# 03_FT2232-jtag.net
KiCad netlist of a schematic drawn in Altium Designer
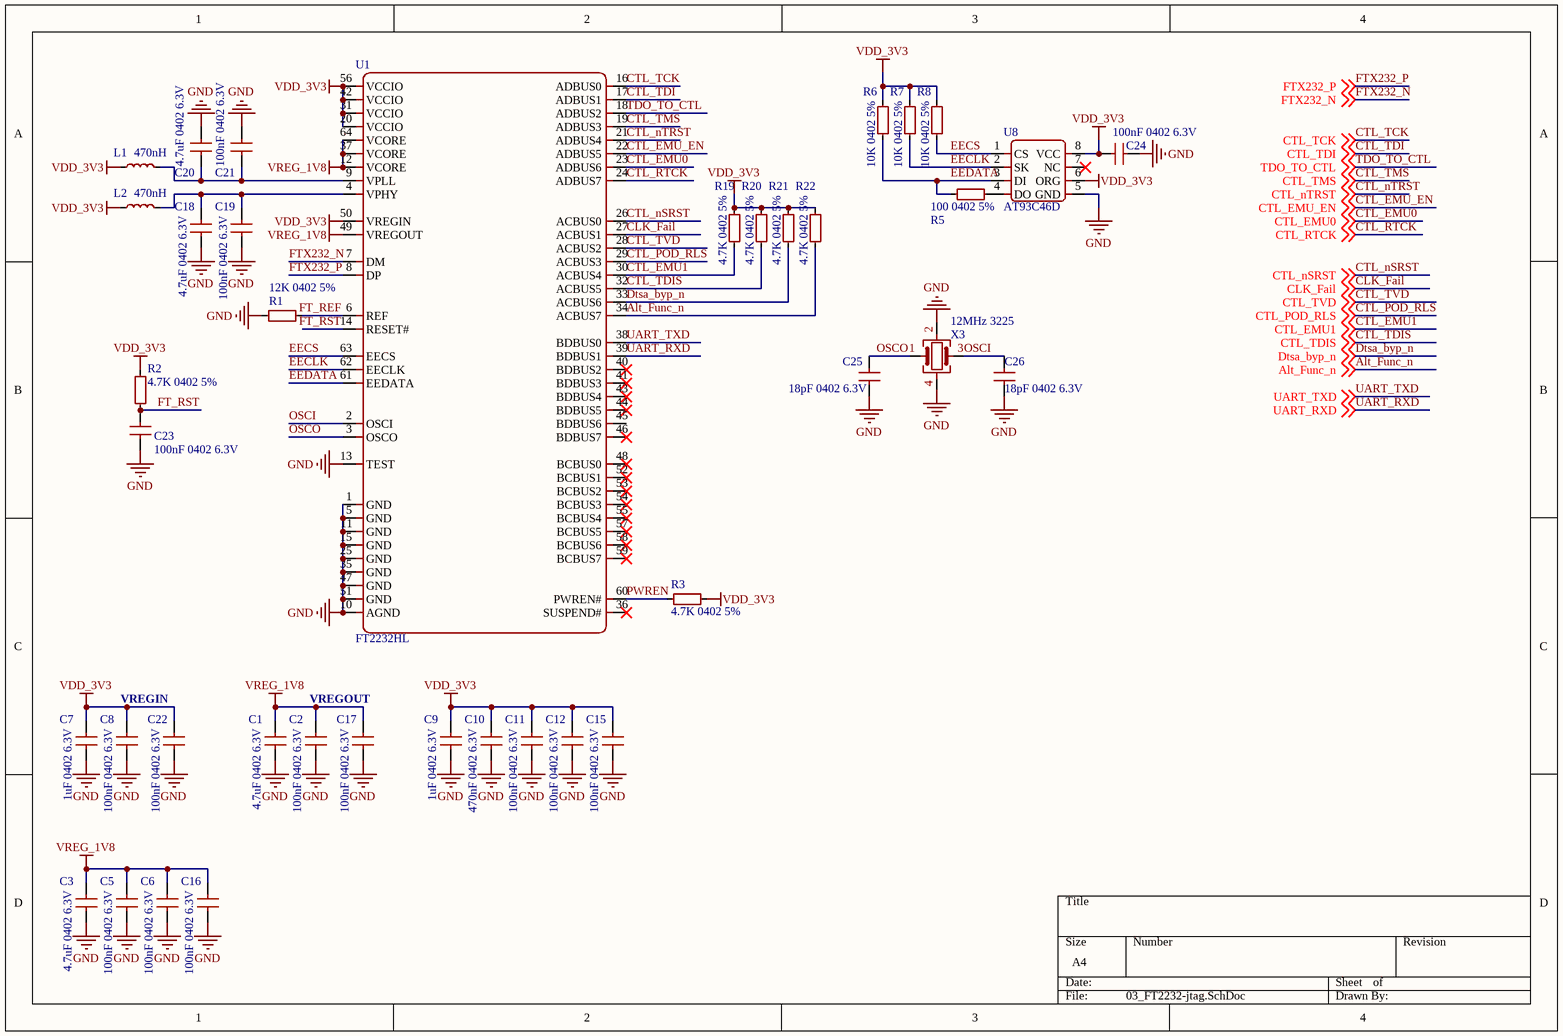
[diagram p0: 03_FT2232-jtag.SchDoc]

(export (version "E")
  (design (tool "Eeschema 10.0.6"))
  (components
    (comp (ref "C1")
      (value "4.7uF 0402 6.3V")
      (footprint "C_0402_1005Metric")
      (description "Unpolarized capacitor")
      (libsource (lib "FPGA_VGA") (part "C"))
    )
    (comp (ref "C2")
      (value "100nF 0402 6.3V")
      (footprint "C_0402_1005Metric")
      (description "Unpolarized capacitor")
      (libsource (lib "FPGA_VGA") (part "C"))
    )
    (comp (ref "C3")
      (value "4.7uF 0402 6.3V")
      (footprint "C_0402_1005Metric")
      (description "Unpolarized capacitor")
      (libsource (lib "FPGA_VGA") (part "C"))
    )
    (comp (ref "C5")
      (value "100nF 0402 6.3V")
      (footprint "C_0402_1005Metric")
      (description "Unpolarized capacitor")
      (libsource (lib "FPGA_VGA") (part "C"))
    )
    (comp (ref "C6")
      (value "100nF 0402 6.3V")
      (footprint "C_0402_1005Metric")
      (description "Unpolarized capacitor")
      (libsource (lib "FPGA_VGA") (part "C"))
    )
    (comp (ref "C7")
      (value "1uF 0402 6.3V")
      (footprint "C_0402_1005Metric")
      (description "Unpolarized capacitor")
      (libsource (lib "FPGA_VGA") (part "C"))
    )
    (comp (ref "C8")
      (value "100nF 0402 6.3V")
      (footprint "C_0402_1005Metric")
      (description "Unpolarized capacitor")
      (libsource (lib "FPGA_VGA") (part "C"))
    )
    (comp (ref "C9")
      (value "1uF 0402 6.3V")
      (footprint "C_0402_1005Metric")
      (description "Unpolarized capacitor")
      (libsource (lib "FPGA_VGA") (part "C"))
    )
    (comp (ref "C10")
      (value "470nF 0402 6.3V")
      (footprint "C_0402_1005Metric")
      (description "Unpolarized capacitor")
      (libsource (lib "FPGA_VGA") (part "C"))
    )
    (comp (ref "C11")
      (value "100nF 0402 6.3V")
      (footprint "C_0402_1005Metric")
      (description "Unpolarized capacitor")
      (libsource (lib "FPGA_VGA") (part "C"))
    )
    (comp (ref "C12")
      (value "100nF 0402 6.3V")
      (footprint "C_0402_1005Metric")
      (description "Unpolarized capacitor")
      (libsource (lib "FPGA_VGA") (part "C"))
    )
    (comp (ref "C15")
      (value "100nF 0402 6.3V")
      (footprint "C_0402_1005Metric")
      (description "Unpolarized capacitor")
      (libsource (lib "FPGA_VGA") (part "C"))
    )
    (comp (ref "C16")
      (value "100nF 0402 6.3V")
      (footprint "C_0402_1005Metric")
      (description "Unpolarized capacitor")
      (libsource (lib "FPGA_VGA") (part "C"))
    )
    (comp (ref "C17")
      (value "100nF 0402 6.3V")
      (footprint "C_0402_1005Metric")
      (description "Unpolarized capacitor")
      (libsource (lib "FPGA_VGA") (part "C"))
    )
    (comp (ref "C18")
      (value "4.7uF 0402 6.3V")
      (footprint "C_0402_1005Metric")
      (description "Unpolarized capacitor")
      (libsource (lib "FPGA_VGA") (part "C"))
    )
    (comp (ref "C19")
      (value "100nF 0402 6.3V")
      (footprint "C_0402_1005Metric")
      (description "Unpolarized capacitor")
      (libsource (lib "FPGA_VGA") (part "C"))
    )
    (comp (ref "C20")
      (value "100nF 0402 6.3V")
      (footprint "C_0402_1005Metric")
      (description "Unpolarized capacitor")
      (libsource (lib "FPGA_VGA") (part "C"))
    )
    (comp (ref "C21")
      (value "4.7uF 0402 6.3V")
      (footprint "C_0402_1005Metric")
      (description "Unpolarized capacitor")
      (libsource (lib "FPGA_VGA") (part "C"))
    )
    (comp (ref "C22")
      (value "100nF 0402 6.3V")
      (footprint "C_0402_1005Metric")
      (description "Unpolarized capacitor")
      (libsource (lib "FPGA_VGA") (part "C"))
    )
    (comp (ref "C23")
      (value "100nF 0402 6.3V")
      (footprint "C_0402_1005Metric")
      (description "Unpolarized capacitor")
      (libsource (lib "FPGA_VGA") (part "C"))
    )
    (comp (ref "C24")
      (value "100nF 0402 6.3V")
      (footprint "C_0402_1005Metric")
      (description "Unpolarized capacitor")
      (libsource (lib "FPGA_VGA") (part "C"))
    )
    (comp (ref "C25")
      (value "18pF 0402 6.3V")
      (footprint "C_0402_1005Metric")
      (description "Unpolarized capacitor")
      (libsource (lib "FPGA_VGA") (part "C"))
    )
    (comp (ref "C26")
      (value "18pF 0402 6.3V")
      (footprint "C_0402_1005Metric")
      (description "Unpolarized capacitor")
      (libsource (lib "FPGA_VGA") (part "C"))
    )
    (comp (ref "L1")
      (value "470nH")
      (footprint "L0402-SMD")
      (description "Inductor")
      (libsource (lib "FPGA_FTX232HL") (part "L"))
    )
    (comp (ref "L2")
      (value "470nH")
      (footprint "L0402-SMD")
      (description "Inductor")
      (libsource (lib "FPGA_FTX232HL") (part "L"))
    )
    (comp (ref "R1")
      (value "12K 0402 5%")
      (footprint "R_0402_1005Metric")
      (description "Resistor")
      (libsource (lib "FPGA_VGA") (part "R"))
    )
    (comp (ref "R2")
      (value "4.7K 0402 5%")
      (footprint "R_0402_1005Metric")
      (description "Resistor")
      (libsource (lib "FPGA_VGA") (part "R"))
    )
    (comp (ref "R3")
      (value "4.7K 0402 5%")
      (footprint "R_0402_1005Metric")
      (description "Resistor")
      (libsource (lib "FPGA_VGA") (part "R"))
    )
    (comp (ref "R5")
      (value "100 0402 5%")
      (footprint "R_0402_1005Metric")
      (description "Resistor")
      (libsource (lib "FPGA_VGA") (part "R"))
    )
    (comp (ref "R6")
      (value "10K 0402 5%")
      (footprint "R_0402_1005Metric")
      (description "Resistor")
      (libsource (lib "FPGA_VGA") (part "R"))
    )
    (comp (ref "R7")
      (value "10K 0402 5%")
      (footprint "R_0402_1005Metric")
      (description "Resistor")
      (libsource (lib "FPGA_VGA") (part "R"))
    )
    (comp (ref "R8")
      (value "10K 0402 5%")
      (footprint "R_0402_1005Metric")
      (description "Resistor")
      (libsource (lib "FPGA_VGA") (part "R"))
    )
    (comp (ref "R19")
      (value "4.7K 0402 5%")
      (footprint "R_0402_1005Metric")
      (description "Resistor")
      (libsource (lib "FPGA_VGA") (part "R"))
    )
    (comp (ref "R20")
      (value "4.7K 0402 5%")
      (footprint "R_0402_1005Metric")
      (description "Resistor")
      (libsource (lib "FPGA_VGA") (part "R"))
    )
    (comp (ref "R21")
      (value "4.7K 0402 5%")
      (footprint "R_0402_1005Metric")
      (description "Resistor")
      (libsource (lib "FPGA_VGA") (part "R"))
    )
    (comp (ref "R22")
      (value "4.7K 0402 5%")
      (footprint "R_0402_1005Metric")
      (description "Resistor")
      (libsource (lib "FPGA_VGA") (part "R"))
    )
    (comp (ref "U1")
      (value "FT2232HL")
      (footprint "FT2232HL-LQFP-64-HD")
      (description "FT2232H Dual High Speed USB to Multipurpose UART/FIFO IC")
      (libsource (lib "XDS100V3-anlogic") (part "FT2232HL"))
    )
    (comp (ref "U8")
      (value "AT93C46D")
      (footprint "AT93C46DN")
      (description "Three-Wire Automotive Temperature Serial EEPROM 1-Kbit")
      (libsource (lib "FPGA_VGA") (part "AT93C46D"))
    )
    (comp (ref "X3")
      (value "12MHz 3225")
      (footprint "Crystal_SMD_3225-4Pin_3.2x2.5mm - duplicate")
      (libsource (lib "FPGA_VGA") (part "Crystal-4Pin-Passive-GND24"))
    )
  )
  (nets
    (net (code "1") (name "/EECLK") (class "Default")
      (node (ref "R7") (pin "2") (pinfunction "2_2") (pintype "passive"))
      (node (ref "U1") (pin "62") (pinfunction "EECLK_62") (pintype "passive"))
      (node (ref "U8") (pin "2") (pinfunction "SK_2") (pintype "passive"))
    )
    (net (code "2") (name "/EECS") (class "Default")
      (node (ref "R8") (pin "2") (pinfunction "2_2") (pintype "passive"))
      (node (ref "U1") (pin "63") (pinfunction "EECS_63") (pintype "passive"))
      (node (ref "U8") (pin "1") (pinfunction "CS_1") (pintype "passive"))
    )
    (net (code "3") (name "/EEDATA") (class "Default")
      (node (ref "R5") (pin "1") (pinfunction "1_1") (pintype "passive"))
      (node (ref "R6") (pin "2") (pinfunction "2_2") (pintype "passive"))
      (node (ref "U1") (pin "61") (pinfunction "EEDATA_61") (pintype "passive"))
      (node (ref "U8") (pin "3") (pinfunction "DI_3") (pintype "passive"))
    )
    (net (code "4") (name "/FT_REF") (class "Default")
      (node (ref "R1") (pin "2") (pinfunction "2_2") (pintype "passive"))
      (node (ref "U1") (pin "6") (pinfunction "REF_6") (pintype "passive"))
    )
    (net (code "5") (name "/FT_RST") (class "Default")
      (node (ref "C23") (pin "2") (pinfunction "2_2") (pintype "passive"))
      (node (ref "R2") (pin "2") (pinfunction "2_2") (pintype "passive"))
      (node (ref "U1") (pin "14") (pinfunction "RESET#_14") (pintype "passive"))
    )
    (net (code "6") (name "/OSCI") (class "Default")
      (node (ref "C26") (pin "1") (pinfunction "1_1") (pintype "passive"))
      (node (ref "U1") (pin "2") (pinfunction "OSCI_2") (pintype "passive"))
      (node (ref "X3") (pin "3") (pinfunction "3_3") (pintype "passive"))
    )
    (net (code "7") (name "/OSCO") (class "Default")
      (node (ref "C25") (pin "1") (pinfunction "1_1") (pintype "passive"))
      (node (ref "U1") (pin "3") (pinfunction "OSCO_3") (pintype "passive"))
      (node (ref "X3") (pin "1") (pinfunction "1_1") (pintype "passive"))
    )
    (net (code "8") (name "/PWREN") (class "Default")
      (node (ref "R3") (pin "2") (pinfunction "2_2") (pintype "passive"))
      (node (ref "U1") (pin "60") (pinfunction "PWREN#_60") (pintype "passive"))
    )
    (net (code "9") (name "Alt_Func_n") (class "Default")
      (node (ref "R22") (pin "1") (pinfunction "1_1") (pintype "passive"))
      (node (ref "U1") (pin "34") (pinfunction "ACBUS7_34") (pintype "passive"))
    )
    (net (code "10") (name "CLK_Fail") (class "Default")
      (node (ref "U1") (pin "27") (pinfunction "ACBUS1_27") (pintype "passive"))
    )
    (net (code "11") (name "CTL_EMU0") (class "Default")
      (node (ref "U1") (pin "23") (pinfunction "ADBUS6_23") (pintype "passive"))
    )
    (net (code "12") (name "CTL_EMU1") (class "Default")
      (node (ref "R19") (pin "1") (pinfunction "1_1") (pintype "passive"))
      (node (ref "U1") (pin "30") (pinfunction "ACBUS4_30") (pintype "passive"))
    )
    (net (code "13") (name "CTL_EMU_EN") (class "Default")
      (node (ref "U1") (pin "22") (pinfunction "ADBUS5_22") (pintype "passive"))
    )
    (net (code "14") (name "CTL_POD_RLS") (class "Default")
      (node (ref "U1") (pin "29") (pinfunction "ACBUS3_29") (pintype "passive"))
    )
    (net (code "15") (name "CTL_RTCK") (class "Default")
      (node (ref "U1") (pin "24") (pinfunction "ADBUS7_24") (pintype "passive"))
    )
    (net (code "16") (name "CTL_TCK") (class "Default")
      (node (ref "U1") (pin "16") (pinfunction "ADBUS0_16") (pintype "passive"))
    )
    (net (code "17") (name "CTL_TDI") (class "Default")
      (node (ref "U1") (pin "17") (pinfunction "ADBUS1_17") (pintype "passive"))
    )
    (net (code "18") (name "CTL_TDIS") (class "Default")
      (node (ref "R20") (pin "1") (pinfunction "1_1") (pintype "passive"))
      (node (ref "U1") (pin "32") (pinfunction "ACBUS5_32") (pintype "passive"))
    )
    (net (code "19") (name "CTL_TMS") (class "Default")
      (node (ref "U1") (pin "19") (pinfunction "ADBUS3_19") (pintype "passive"))
    )
    (net (code "20") (name "CTL_TVD") (class "Default")
      (node (ref "U1") (pin "28") (pinfunction "ACBUS2_28") (pintype "passive"))
    )
    (net (code "21") (name "CTL_nSRST") (class "Default")
      (node (ref "U1") (pin "26") (pinfunction "ACBUS0_26") (pintype "passive"))
    )
    (net (code "22") (name "CTL_nTRST") (class "Default")
      (node (ref "U1") (pin "21") (pinfunction "ADBUS4_21") (pintype "passive"))
    )
    (net (code "23") (name "Dtsa_byp_n") (class "Default")
      (node (ref "R21") (pin "1") (pinfunction "1_1") (pintype "passive"))
      (node (ref "U1") (pin "33") (pinfunction "ACBUS6_33") (pintype "passive"))
    )
    (net (code "24") (name "FTX232_N") (class "Default")
      (node (ref "U1") (pin "7") (pinfunction "DM_7") (pintype "passive"))
    )
    (net (code "25") (name "FTX232_P") (class "Default")
      (node (ref "U1") (pin "8") (pinfunction "DP_8") (pintype "passive"))
    )
    (net (code "26") (name "GND") (class "Default")
      (node (ref "C1") (pin "1") (pinfunction "1_1") (pintype "passive"))
      (node (ref "C10") (pin "1") (pinfunction "1_1") (pintype "passive"))
      (node (ref "C11") (pin "1") (pinfunction "1_1") (pintype "passive"))
      (node (ref "C12") (pin "1") (pinfunction "1_1") (pintype "passive"))
      (node (ref "C15") (pin "1") (pinfunction "1_1") (pintype "passive"))
      (node (ref "C16") (pin "1") (pinfunction "1_1") (pintype "passive"))
      (node (ref "C17") (pin "1") (pinfunction "1_1") (pintype "passive"))
      (node (ref "C18") (pin "1") (pinfunction "1_1") (pintype "passive"))
      (node (ref "C19") (pin "1") (pinfunction "1_1") (pintype "passive"))
      (node (ref "C2") (pin "1") (pinfunction "1_1") (pintype "passive"))
      (node (ref "C20") (pin "1") (pinfunction "1_1") (pintype "passive"))
      (node (ref "C21") (pin "1") (pinfunction "1_1") (pintype "passive"))
      (node (ref "C22") (pin "1") (pinfunction "1_1") (pintype "passive"))
      (node (ref "C23") (pin "1") (pinfunction "1_1") (pintype "passive"))
      (node (ref "C24") (pin "2") (pinfunction "2_2") (pintype "passive"))
      (node (ref "C25") (pin "2") (pinfunction "2_2") (pintype "passive"))
      (node (ref "C26") (pin "2") (pinfunction "2_2") (pintype "passive"))
      (node (ref "C3") (pin "1") (pinfunction "1_1") (pintype "passive"))
      (node (ref "C5") (pin "1") (pinfunction "1_1") (pintype "passive"))
      (node (ref "C6") (pin "1") (pinfunction "1_1") (pintype "passive"))
      (node (ref "C7") (pin "1") (pinfunction "1_1") (pintype "passive"))
      (node (ref "C8") (pin "1") (pinfunction "1_1") (pintype "passive"))
      (node (ref "C9") (pin "1") (pinfunction "1_1") (pintype "passive"))
      (node (ref "R1") (pin "1") (pinfunction "1_1") (pintype "passive"))
      (node (ref "U1") (pin "1") (pinfunction "GND_1") (pintype "passive"))
      (node (ref "U1") (pin "10") (pinfunction "AGND_10") (pintype "passive"))
      (node (ref "U1") (pin "11") (pinfunction "GND_11") (pintype "passive"))
      (node (ref "U1") (pin "13") (pinfunction "TEST_13") (pintype "passive"))
      (node (ref "U1") (pin "15") (pinfunction "GND_15") (pintype "passive"))
      (node (ref "U1") (pin "25") (pinfunction "GND_25") (pintype "passive"))
      (node (ref "U1") (pin "35") (pinfunction "GND_35") (pintype "passive"))
      (node (ref "U1") (pin "47") (pinfunction "GND_47") (pintype "passive"))
      (node (ref "U1") (pin "5") (pinfunction "GND_5") (pintype "passive"))
      (node (ref "U1") (pin "51") (pinfunction "GND_51") (pintype "passive"))
      (node (ref "U8") (pin "5") (pinfunction "GND_5") (pintype "passive"))
      (node (ref "X3") (pin "2") (pinfunction "2_2") (pintype "passive"))
      (node (ref "X3") (pin "4") (pinfunction "4_4") (pintype "passive"))
    )
    (net (code "27") (name "Net-(U1-VPHY)") (class "Default")
      (node (ref "C18") (pin "2") (pinfunction "2_2") (pintype "passive"))
      (node (ref "C19") (pin "2") (pinfunction "2_2") (pintype "passive"))
      (node (ref "L2") (pin "2") (pinfunction "2_2") (pintype "passive"))
      (node (ref "U1") (pin "4") (pinfunction "VPHY_4") (pintype "passive"))
    )
    (net (code "28") (name "Net-(U1-VPLL)") (class "Default")
      (node (ref "C20") (pin "2") (pinfunction "2_2") (pintype "passive"))
      (node (ref "C21") (pin "2") (pinfunction "2_2") (pintype "passive"))
      (node (ref "L1") (pin "2") (pinfunction "2_2") (pintype "passive"))
      (node (ref "U1") (pin "9") (pinfunction "VPLL_9") (pintype "passive"))
    )
    (net (code "29") (name "Net-(U8-DO)") (class "Default")
      (node (ref "R5") (pin "2") (pinfunction "2_2") (pintype "passive"))
      (node (ref "U8") (pin "4") (pinfunction "DO_4") (pintype "passive"))
    )
    (net (code "30") (name "TDO_TO_CTL") (class "Default")
      (node (ref "U1") (pin "18") (pinfunction "ADBUS2_18") (pintype "passive"))
    )
    (net (code "31") (name "UART_RXD") (class "Default")
      (node (ref "U1") (pin "39") (pinfunction "BDBUS1_39") (pintype "passive"))
    )
    (net (code "32") (name "UART_TXD") (class "Default")
      (node (ref "U1") (pin "38") (pinfunction "BDBUS0_38") (pintype "passive"))
    )
    (net (code "33") (name "VDD_3V3") (class "Default")
      (node (ref "C10") (pin "2") (pinfunction "2_2") (pintype "passive"))
      (node (ref "C11") (pin "2") (pinfunction "2_2") (pintype "passive"))
      (node (ref "C12") (pin "2") (pinfunction "2_2") (pintype "passive"))
      (node (ref "C15") (pin "2") (pinfunction "2_2") (pintype "passive"))
      (node (ref "C22") (pin "2") (pinfunction "2_2") (pintype "passive"))
      (node (ref "C24") (pin "1") (pinfunction "1_1") (pintype "passive"))
      (node (ref "C7") (pin "2") (pinfunction "2_2") (pintype "passive"))
      (node (ref "C8") (pin "2") (pinfunction "2_2") (pintype "passive"))
      (node (ref "C9") (pin "2") (pinfunction "2_2") (pintype "passive"))
      (node (ref "L1") (pin "1") (pinfunction "1_1") (pintype "passive"))
      (node (ref "L2") (pin "1") (pinfunction "1_1") (pintype "passive"))
      (node (ref "R19") (pin "2") (pinfunction "2_2") (pintype "passive"))
      (node (ref "R2") (pin "1") (pinfunction "1_1") (pintype "passive"))
      (node (ref "R20") (pin "2") (pinfunction "2_2") (pintype "passive"))
      (node (ref "R21") (pin "2") (pinfunction "2_2") (pintype "passive"))
      (node (ref "R22") (pin "2") (pinfunction "2_2") (pintype "passive"))
      (node (ref "R3") (pin "1") (pinfunction "1_1") (pintype "passive"))
      (node (ref "R6") (pin "1") (pinfunction "1_1") (pintype "passive"))
      (node (ref "R7") (pin "1") (pinfunction "1_1") (pintype "passive"))
      (node (ref "R8") (pin "1") (pinfunction "1_1") (pintype "passive"))
      (node (ref "U1") (pin "20") (pinfunction "VCCIO_20") (pintype "passive"))
      (node (ref "U1") (pin "31") (pinfunction "VCCIO_31") (pintype "passive"))
      (node (ref "U1") (pin "42") (pinfunction "VCCIO_42") (pintype "passive"))
      (node (ref "U1") (pin "50") (pinfunction "VREGIN_50") (pintype "passive"))
      (node (ref "U1") (pin "56") (pinfunction "VCCIO_56") (pintype "passive"))
      (node (ref "U8") (pin "6") (pinfunction "ORG_6") (pintype "passive"))
      (node (ref "U8") (pin "8") (pinfunction "VCC_8") (pintype "passive"))
    )
    (net (code "34") (name "VREG_1V8") (class "Default")
      (node (ref "C1") (pin "2") (pinfunction "2_2") (pintype "passive"))
      (node (ref "C16") (pin "2") (pinfunction "2_2") (pintype "passive"))
      (node (ref "C17") (pin "2") (pinfunction "2_2") (pintype "passive"))
      (node (ref "C2") (pin "2") (pinfunction "2_2") (pintype "passive"))
      (node (ref "C3") (pin "2") (pinfunction "2_2") (pintype "passive"))
      (node (ref "C5") (pin "2") (pinfunction "2_2") (pintype "passive"))
      (node (ref "C6") (pin "2") (pinfunction "2_2") (pintype "passive"))
      (node (ref "U1") (pin "12") (pinfunction "VCORE_12") (pintype "passive"))
      (node (ref "U1") (pin "37") (pinfunction "VCORE_37") (pintype "passive"))
      (node (ref "U1") (pin "49") (pinfunction "VREGOUT_49") (pintype "passive"))
      (node (ref "U1") (pin "64") (pinfunction "VCORE_64") (pintype "passive"))
    )
    (net (code "35") (name "unconnected-(U1-BCBUS0-Pad48)") (class "Default")
      (node (ref "U1") (pin "48") (pinfunction "BCBUS0_48") (pintype "passive+no_connect"))
    )
    (net (code "36") (name "unconnected-(U1-BCBUS1-Pad52)") (class "Default")
      (node (ref "U1") (pin "52") (pinfunction "BCBUS1_52") (pintype "passive+no_connect"))
    )
    (net (code "37") (name "unconnected-(U1-BCBUS2-Pad53)") (class "Default")
      (node (ref "U1") (pin "53") (pinfunction "BCBUS2_53") (pintype "passive+no_connect"))
    )
    (net (code "38") (name "unconnected-(U1-BCBUS3-Pad54)") (class "Default")
      (node (ref "U1") (pin "54") (pinfunction "BCBUS3_54") (pintype "passive+no_connect"))
    )
    (net (code "39") (name "unconnected-(U1-BCBUS4-Pad55)") (class "Default")
      (node (ref "U1") (pin "55") (pinfunction "BCBUS4_55") (pintype "passive+no_connect"))
    )
    (net (code "40") (name "unconnected-(U1-BCBUS5-Pad57)") (class "Default")
      (node (ref "U1") (pin "57") (pinfunction "BCBUS5_57") (pintype "passive+no_connect"))
    )
    (net (code "41") (name "unconnected-(U1-BCBUS6-Pad58)") (class "Default")
      (node (ref "U1") (pin "58") (pinfunction "BCBUS6_58") (pintype "passive+no_connect"))
    )
    (net (code "42") (name "unconnected-(U1-BCBUS7-Pad59)") (class "Default")
      (node (ref "U1") (pin "59") (pinfunction "BCBUS7_59") (pintype "passive+no_connect"))
    )
    (net (code "43") (name "unconnected-(U1-BDBUS2-Pad40)") (class "Default")
      (node (ref "U1") (pin "40") (pinfunction "BDBUS2_40") (pintype "passive+no_connect"))
    )
    (net (code "44") (name "unconnected-(U1-BDBUS3-Pad41)") (class "Default")
      (node (ref "U1") (pin "41") (pinfunction "BDBUS3_41") (pintype "passive+no_connect"))
    )
    (net (code "45") (name "unconnected-(U1-BDBUS4-Pad43)") (class "Default")
      (node (ref "U1") (pin "43") (pinfunction "BDBUS4_43") (pintype "passive+no_connect"))
    )
    (net (code "46") (name "unconnected-(U1-BDBUS5-Pad44)") (class "Default")
      (node (ref "U1") (pin "44") (pinfunction "BDBUS5_44") (pintype "passive+no_connect"))
    )
    (net (code "47") (name "unconnected-(U1-BDBUS6-Pad45)") (class "Default")
      (node (ref "U1") (pin "45") (pinfunction "BDBUS6_45") (pintype "passive"))
    )
    (net (code "48") (name "unconnected-(U1-BDBUS7-Pad46)") (class "Default")
      (node (ref "U1") (pin "46") (pinfunction "BDBUS7_46") (pintype "passive+no_connect"))
    )
    (net (code "49") (name "unconnected-(U1-SUSPEND#-Pad36)") (class "Default")
      (node (ref "U1") (pin "36") (pinfunction "SUSPEND#_36") (pintype "passive+no_connect"))
    )
    (net (code "50") (name "unconnected-(U8-NC-Pad7)") (class "Default")
      (node (ref "U8") (pin "7") (pinfunction "NC_7") (pintype "passive+no_connect"))
    )
  )
)
